# RLY_INVERTER.net
KiCad netlist of a schematic drawn in EAGLE
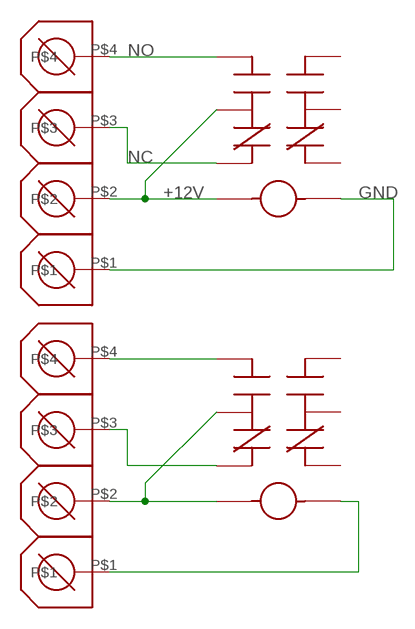
[diagram p0: schematic, sheet 1]

(export (version "E")
  (design (tool "Eeschema 10.0.6"))
  (components
    (comp (ref "J1")
      (value "TE_282834-4")
      (footprint "eagle-import:282834-4_FOOT")
      (libsource (lib "eagle-import") (part "TE_282834-4"))
    )
    (comp (ref "J2")
      (value "TE_282834-4")
      (footprint "eagle-import:282834-4_FOOT")
      (libsource (lib "eagle-import") (part "TE_282834-4"))
    )
    (comp (ref "U$1")
      (value "BSPD_PARTS_RLY_V23079A1001B301")
      (footprint "eagle-import:BSPD_PARTS_V23079F1101B301")
      (libsource (lib "eagle-import") (part "BSPD_PARTS_RLY_V23079A1001B301"))
    )
    (comp (ref "U$2")
      (value "BSPD_PARTS_RLY_V23079A1001B301")
      (footprint "eagle-import:BSPD_PARTS_V23079F1101B301")
      (libsource (lib "eagle-import") (part "BSPD_PARTS_RLY_V23079A1001B301"))
    )
  )
  (nets
    (net (code "1") (name "/+12V") (class "Default")
      (node (ref "J2") (pin "P$2") (pinfunction "P$2_P$2") (pintype "bidirectional"))
      (node (ref "U$2") (pin "1") (pinfunction "1_1") (pintype "bidirectional"))
      (node (ref "U$2") (pin "4") (pinfunction "4_4") (pintype "bidirectional"))
    )
    (net (code "2") (name "/GND") (class "Default")
      (node (ref "J2") (pin "P$1") (pinfunction "P$1_P$1") (pintype "bidirectional"))
      (node (ref "U$2") (pin "12") (pinfunction "12_12") (pintype "bidirectional"))
    )
    (net (code "3") (name "/NC") (class "Default")
      (node (ref "J2") (pin "P$3") (pinfunction "P$3_P$3") (pintype "bidirectional"))
      (node (ref "U$2") (pin "3") (pinfunction "3_3") (pintype "bidirectional"))
    )
    (net (code "4") (name "/NO") (class "Default")
      (node (ref "J2") (pin "P$4") (pinfunction "P$4_P$4") (pintype "bidirectional"))
      (node (ref "U$2") (pin "5") (pinfunction "5_5") (pintype "bidirectional"))
    )
    (net (code "5") (name "Net-(J1-PadP$1)") (class "Default")
      (node (ref "J1") (pin "P$1") (pinfunction "P$1_P$1") (pintype "bidirectional"))
      (node (ref "U$1") (pin "12") (pinfunction "12_12") (pintype "bidirectional"))
    )
    (net (code "6") (name "Net-(J1-PadP$2)") (class "Default")
      (node (ref "J1") (pin "P$2") (pinfunction "P$2_P$2") (pintype "bidirectional"))
      (node (ref "U$1") (pin "1") (pinfunction "1_1") (pintype "bidirectional"))
      (node (ref "U$1") (pin "4") (pinfunction "4_4") (pintype "bidirectional"))
    )
    (net (code "7") (name "Net-(J1-PadP$3)") (class "Default")
      (node (ref "J1") (pin "P$3") (pinfunction "P$3_P$3") (pintype "bidirectional"))
      (node (ref "U$1") (pin "3") (pinfunction "3_3") (pintype "bidirectional"))
    )
    (net (code "8") (name "Net-(J1-PadP$4)") (class "Default")
      (node (ref "J1") (pin "P$4") (pinfunction "P$4_P$4") (pintype "bidirectional"))
      (node (ref "U$1") (pin "5") (pinfunction "5_5") (pintype "bidirectional"))
    )
    (net (code "9") (name "unconnected-(U$1-Pad8)") (class "Default")
      (node (ref "U$1") (pin "8") (pinfunction "8_8") (pintype "bidirectional"))
    )
    (net (code "10") (name "unconnected-(U$1-Pad9)") (class "Default")
      (node (ref "U$1") (pin "9") (pinfunction "9_9") (pintype "bidirectional"))
    )
    (net (code "11") (name "unconnected-(U$1-Pad10)") (class "Default")
      (node (ref "U$1") (pin "10") (pinfunction "10_10") (pintype "bidirectional"))
    )
    (net (code "12") (name "unconnected-(U$2-Pad8)") (class "Default")
      (node (ref "U$2") (pin "8") (pinfunction "8_8") (pintype "bidirectional"))
    )
    (net (code "13") (name "unconnected-(U$2-Pad9)") (class "Default")
      (node (ref "U$2") (pin "9") (pinfunction "9_9") (pintype "bidirectional"))
    )
    (net (code "14") (name "unconnected-(U$2-Pad10)") (class "Default")
      (node (ref "U$2") (pin "10") (pinfunction "10_10") (pintype "bidirectional"))
    )
  )
)
